# design.net
KiCad netlist of a schematic drawn in EasyEDA Pro
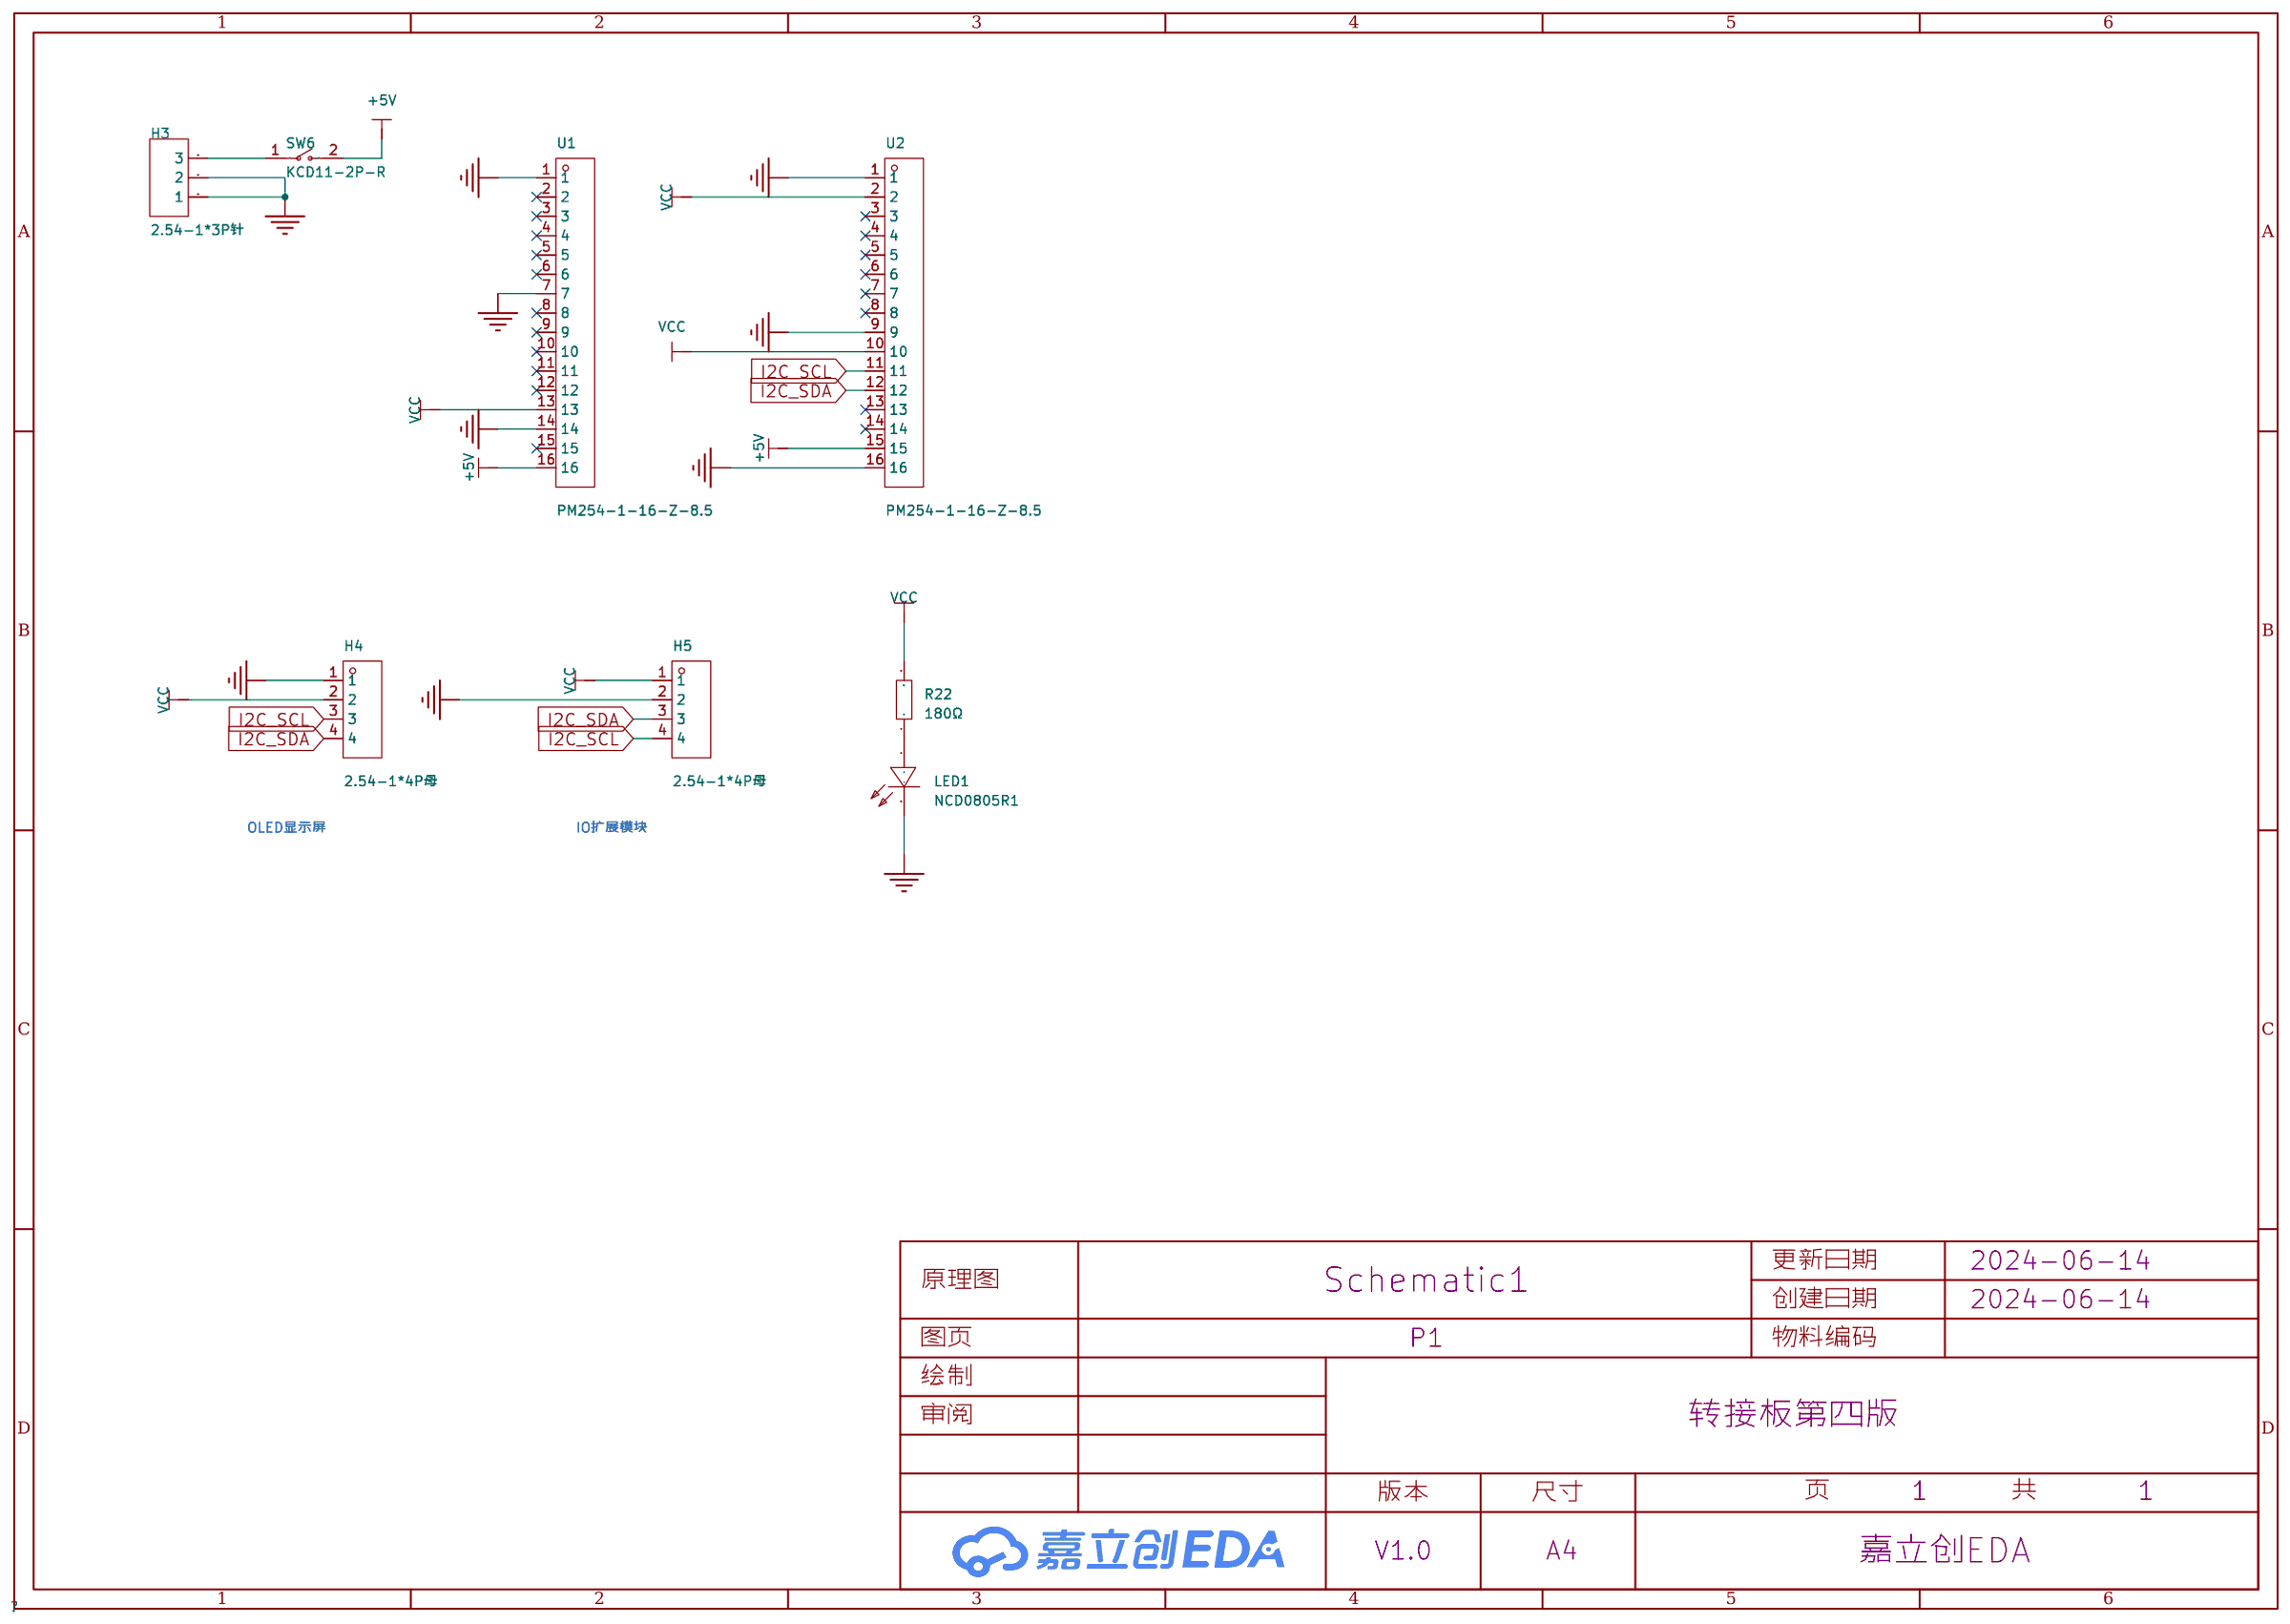
[diagram p0: schematic sheet]

(export (version "E")
  (design (tool "Eeschema 10.0.6"))
  (components
    (comp (ref "H3")
      (value "2.54-1*3P针")
      (footprint "easyedapro:HDR-TH_3P-P2.54-V-M-1")
      (fields (field (name "Manufacturer") "BOOMELE(博穆精密)"))
      (libsource (lib "easyedapro") (part "Header-Male-2.54_1x3"))
    )
    (comp (ref "H4")
      (value "2.54-1*4P母")
      (footprint "easyedapro:HDR-TH_4P-P2.54-V-F")
      (fields (field (name "Manufacturer") "BOOMELE(博穆精密)"))
      (libsource (lib "easyedapro") (part "2.54-1*4P母"))
    )
    (comp (ref "H5")
      (value "2.54-1*4P母")
      (footprint "easyedapro:HDR-TH_4P-P2.54-V-F")
      (fields (field (name "Manufacturer") "BOOMELE(博穆精密)"))
      (libsource (lib "easyedapro") (part "2.54-1*4P母"))
    )
    (comp (ref "LED1")
      (value "NCD0805R1")
      (footprint "easyedapro:LED0805-R-RD")
      (fields (field (name "Manufacturer") "国星光电"))
      (libsource (lib "easyedapro") (part "FC-2012HRK-620D"))
    )
    (comp (ref "R22")
      (value "180Ω")
      (footprint "easyedapro:R0805")
      (description "电阻类型:厚膜电阻;阻值:180Ω;精度:±1%;功率:125mW;最大工作电压:150V;温度系数:±100ppm/°C;")
      (fields
        (field (name "Manufacturer Part") "0805W8F1800T5E")
        (field (name "Manufacturer") "UNI-ROYAL(厚声)")
      )
      (libsource (lib "easyedapro") (part "0805W8F1800T5E"))
    )
    (comp (ref "SW6")
      (value "KCD11-2P-R")
      (footprint "easyedapro:SW-TH_2P-L15.0-W10.5-P5.00_KCD11-2P-R")
      (description "带灯:无;引脚样式:焊片;额定电流:3A;额定电压(AC):250V;额定电压(DC):-;电路结构:单刀单掷;机械寿命:1万次;")
      (fields (field (name "Manufacturer") "SHOU HAN(首韩)"))
      (libsource (lib "easyedapro") (part "KCD11-2P-R"))
    )
    (comp (ref "U1")
      (value "PM254-1-16-Z-8.5")
      (footprint "easyedapro:HDR-TH_16P-P2.54-V-F-A")
      (fields (field (name "Manufacturer") "HCTL(华灿天禄)"))
      (libsource (lib "easyedapro") (part "PM254-1-16-Z-8.5"))
    )
    (comp (ref "U2")
      (value "PM254-1-16-Z-8.5")
      (footprint "easyedapro:HDR-TH_16P-P2.54-V-F-A")
      (fields (field (name "Manufacturer") "HCTL(华灿天禄)"))
      (libsource (lib "easyedapro") (part "PM254-1-16-Z-8.5"))
    )
  )
  (nets
    (net (code "1") (name "+5V") (class "Default")
      (node (ref "SW6") (pin "2") (pinfunction "2_2") (pintype "unspecified"))
      (node (ref "U1") (pin "16") (pinfunction "16_16") (pintype "unspecified"))
      (node (ref "U2") (pin "15") (pinfunction "15_15") (pintype "unspecified"))
    )
    (net (code "2") (name "GND") (class "Default")
      (node (ref "H3") (pin "1") (pinfunction "1_1") (pintype "input"))
      (node (ref "H3") (pin "2") (pinfunction "2_2") (pintype "input"))
      (node (ref "H4") (pin "1") (pinfunction "1_1") (pintype "unspecified"))
      (node (ref "H5") (pin "2") (pinfunction "2_2") (pintype "unspecified"))
      (node (ref "LED1") (pin "2") (pinfunction "-_2") (pintype "unspecified"))
      (node (ref "U1") (pin "1") (pinfunction "1_1") (pintype "unspecified"))
      (node (ref "U1") (pin "14") (pinfunction "14_14") (pintype "unspecified"))
      (node (ref "U1") (pin "7") (pinfunction "7_7") (pintype "unspecified"))
      (node (ref "U2") (pin "1") (pinfunction "1_1") (pintype "unspecified"))
      (node (ref "U2") (pin "16") (pinfunction "16_16") (pintype "unspecified"))
      (node (ref "U2") (pin "9") (pinfunction "9_9") (pintype "unspecified"))
    )
    (net (code "3") (name "I2C_SCL") (class "Default")
      (node (ref "H4") (pin "3") (pinfunction "3_3") (pintype "unspecified"))
      (node (ref "H5") (pin "4") (pinfunction "4_4") (pintype "unspecified"))
      (node (ref "U2") (pin "11") (pinfunction "11_11") (pintype "unspecified"))
    )
    (net (code "4") (name "I2C_SDA") (class "Default")
      (node (ref "H4") (pin "4") (pinfunction "4_4") (pintype "unspecified"))
      (node (ref "H5") (pin "3") (pinfunction "3_3") (pintype "unspecified"))
      (node (ref "U2") (pin "12") (pinfunction "12_12") (pintype "unspecified"))
    )
    (net (code "5") (name "Net-(H3-Pad3)") (class "Default")
      (node (ref "H3") (pin "3") (pinfunction "3_3") (pintype "input"))
      (node (ref "SW6") (pin "1") (pinfunction "1_1") (pintype "unspecified"))
    )
    (net (code "6") (name "Net-(LED1-+)") (class "Default")
      (node (ref "LED1") (pin "1") (pinfunction "+_1") (pintype "unspecified"))
      (node (ref "R22") (pin "1") (pinfunction "1_1") (pintype "input"))
    )
    (net (code "7") (name "VCC") (class "Default")
      (node (ref "H4") (pin "2") (pinfunction "2_2") (pintype "unspecified"))
      (node (ref "H5") (pin "1") (pinfunction "1_1") (pintype "unspecified"))
      (node (ref "R22") (pin "2") (pinfunction "2_2") (pintype "input"))
      (node (ref "U1") (pin "13") (pinfunction "13_13") (pintype "unspecified"))
      (node (ref "U2") (pin "10") (pinfunction "10_10") (pintype "unspecified"))
      (node (ref "U2") (pin "2") (pinfunction "2_2") (pintype "unspecified"))
    )
    (net (code "8") (name "unconnected-(U1-Pad2)") (class "Default")
      (node (ref "U1") (pin "2") (pinfunction "2_2") (pintype "unspecified+no_connect"))
    )
    (net (code "9") (name "unconnected-(U1-Pad3)") (class "Default")
      (node (ref "U1") (pin "3") (pinfunction "3_3") (pintype "unspecified+no_connect"))
    )
    (net (code "10") (name "unconnected-(U1-Pad4)") (class "Default")
      (node (ref "U1") (pin "4") (pinfunction "4_4") (pintype "unspecified+no_connect"))
    )
    (net (code "11") (name "unconnected-(U1-Pad5)") (class "Default")
      (node (ref "U1") (pin "5") (pinfunction "5_5") (pintype "unspecified+no_connect"))
    )
    (net (code "12") (name "unconnected-(U1-Pad6)") (class "Default")
      (node (ref "U1") (pin "6") (pinfunction "6_6") (pintype "unspecified+no_connect"))
    )
    (net (code "13") (name "unconnected-(U1-Pad8)") (class "Default")
      (node (ref "U1") (pin "8") (pinfunction "8_8") (pintype "unspecified+no_connect"))
    )
    (net (code "14") (name "unconnected-(U1-Pad9)") (class "Default")
      (node (ref "U1") (pin "9") (pinfunction "9_9") (pintype "unspecified+no_connect"))
    )
    (net (code "15") (name "unconnected-(U1-Pad10)") (class "Default")
      (node (ref "U1") (pin "10") (pinfunction "10_10") (pintype "unspecified+no_connect"))
    )
    (net (code "16") (name "unconnected-(U1-Pad11)") (class "Default")
      (node (ref "U1") (pin "11") (pinfunction "11_11") (pintype "unspecified+no_connect"))
    )
    (net (code "17") (name "unconnected-(U1-Pad12)") (class "Default")
      (node (ref "U1") (pin "12") (pinfunction "12_12") (pintype "unspecified+no_connect"))
    )
    (net (code "18") (name "unconnected-(U1-Pad15)") (class "Default")
      (node (ref "U1") (pin "15") (pinfunction "15_15") (pintype "unspecified+no_connect"))
    )
    (net (code "19") (name "unconnected-(U2-Pad3)") (class "Default")
      (node (ref "U2") (pin "3") (pinfunction "3_3") (pintype "unspecified+no_connect"))
    )
    (net (code "20") (name "unconnected-(U2-Pad4)") (class "Default")
      (node (ref "U2") (pin "4") (pinfunction "4_4") (pintype "unspecified+no_connect"))
    )
    (net (code "21") (name "unconnected-(U2-Pad5)") (class "Default")
      (node (ref "U2") (pin "5") (pinfunction "5_5") (pintype "unspecified+no_connect"))
    )
    (net (code "22") (name "unconnected-(U2-Pad6)") (class "Default")
      (node (ref "U2") (pin "6") (pinfunction "6_6") (pintype "unspecified+no_connect"))
    )
    (net (code "23") (name "unconnected-(U2-Pad7)") (class "Default")
      (node (ref "U2") (pin "7") (pinfunction "7_7") (pintype "unspecified+no_connect"))
    )
    (net (code "24") (name "unconnected-(U2-Pad8)") (class "Default")
      (node (ref "U2") (pin "8") (pinfunction "8_8") (pintype "unspecified+no_connect"))
    )
    (net (code "25") (name "unconnected-(U2-Pad13)") (class "Default")
      (node (ref "U2") (pin "13") (pinfunction "13_13") (pintype "unspecified+no_connect"))
    )
    (net (code "26") (name "unconnected-(U2-Pad14)") (class "Default")
      (node (ref "U2") (pin "14") (pinfunction "14_14") (pintype "unspecified+no_connect"))
    )
  )
)
